# Main.net
KiCad netlist of a schematic drawn in Altium Designer
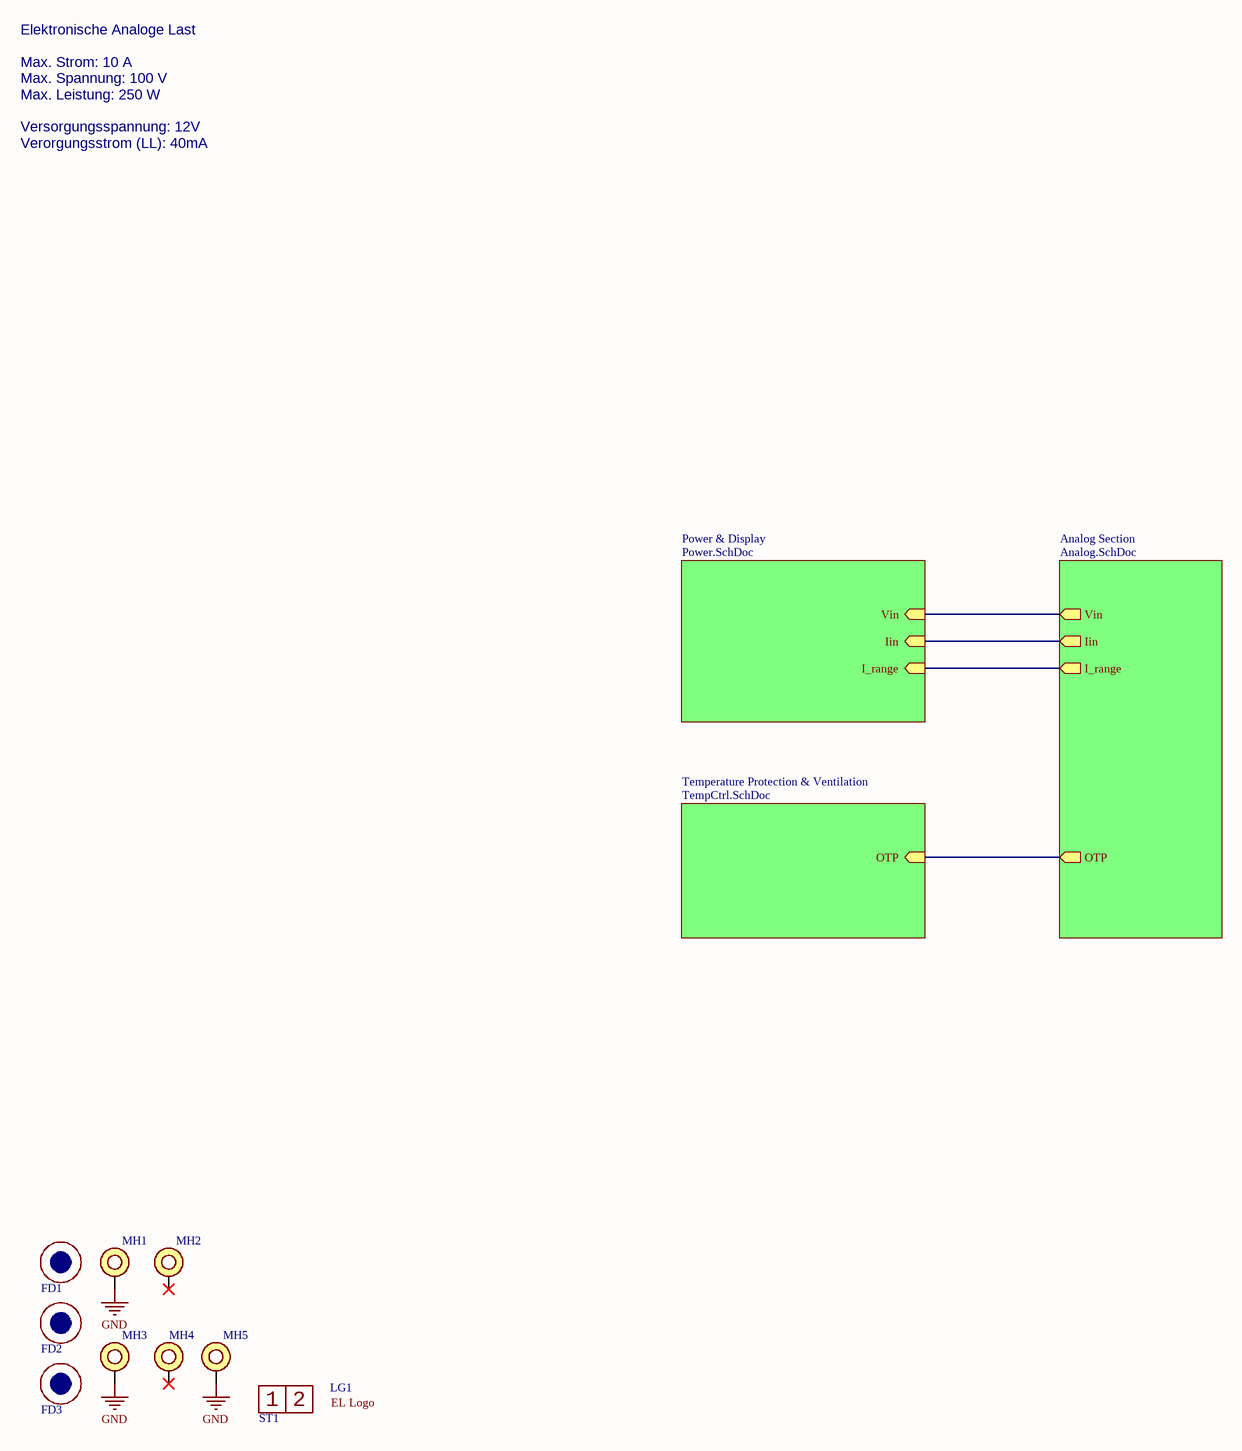
[diagram p0: Main.SchDoc]

(export (version "E")
  (design (tool "Eeschema 10.0.6"))
  (components
    (comp (ref "FD1")
      (value "Fiducial Mark 1mm")
      (footprint "Mech Fiducial 1mm")
      (description "Mech Fiducial Mark 1mm")
      (libsource (lib "SchLibrary") (part "Mech Fiducial"))
    )
    (comp (ref "FD2")
      (value "Fiducial Mark 1mm")
      (footprint "Mech Fiducial 1mm")
      (description "Mech Fiducial Mark 1mm")
      (libsource (lib "SchLibrary") (part "Mech Fiducial"))
    )
    (comp (ref "FD3")
      (value "Fiducial Mark 1mm")
      (footprint "Mech Fiducial 1mm")
      (description "Mech Fiducial Mark 1mm")
      (libsource (lib "SchLibrary") (part "Mech Fiducial"))
    )
    (comp (ref "LG1")
      (value "EL Logo")
      (footprint "Mech Logo EL")
      (description "Mech Logo EL Top Layer")
      (libsource (lib "SchLibrary") (part "Mech Logo EL"))
    )
    (comp (ref "MH1")
      (value "3.4mm")
      (footprint "Mech Hole 3.4mm Plated & Restring")
      (description "Mech Hole 3.4mm for M3 Plated & Restring")
      (libsource (lib "SchLibrary") (part "Mech Hole 3.4mm Pltd Restring 7mm"))
    )
    (comp (ref "MH2")
      (value "3.4mm")
      (footprint "Mech Hole 3.4mm Plated & Restring")
      (description "Mech Hole 3.4mm for M3 Plated & Restring")
      (libsource (lib "SchLibrary") (part "Mech Hole 3.4mm Pltd Restring 7mm"))
    )
    (comp (ref "MH3")
      (value "3.4mm")
      (footprint "Mech Hole 3.4mm Plated & Restring")
      (description "Mech Hole 3.4mm for M3 Plated & Restring")
      (libsource (lib "SchLibrary") (part "Mech Hole 3.4mm Pltd Restring 7mm"))
    )
    (comp (ref "MH4")
      (value "3.4mm")
      (footprint "Mech Hole 3.4mm Plated & Restring")
      (description "Mech Hole 3.4mm for M3 Plated & Restring")
      (libsource (lib "SchLibrary") (part "Mech Hole 3.4mm Pltd Restring 7mm"))
    )
    (comp (ref "MH5")
      (value "3.4mm")
      (footprint "Mech Hole 3.4mm Plated & Restring")
      (description "Mech Hole 3.4mm for M3 Plated & Restring")
      (libsource (lib "SchLibrary") (part "Mech Hole 3.4mm Pltd Restring 7mm"))
    )
    (comp (ref "ST1")
      (value "Layer Window 2")
      (footprint "Mech Layer Count 2")
      (description "Mech Layer Count 2 Layers")
      (libsource (lib "CustomLib") (part "Mech Layer Count 2"))
    )
  )
  (nets
    (net (code "5") (name "GND") (class "Default")
      (node (ref "MH1") (pin "1") (pinfunction "1_1") (pintype "power_in"))
      (node (ref "MH3") (pin "1") (pinfunction "1_1") (pintype "power_in"))
      (node (ref "MH5") (pin "1") (pinfunction "1_1") (pintype "power_in"))
    )
    (net (code "6") (name "unconnected-(FD1-Pad0)") (class "Default")
      (node (ref "FD1") (pin "0") (pinfunction "0_0") (pintype "passive"))
    )
    (net (code "7") (name "unconnected-(FD2-Pad0)") (class "Default")
      (node (ref "FD2") (pin "0") (pinfunction "0_0") (pintype "passive"))
    )
    (net (code "8") (name "unconnected-(FD3-Pad0)") (class "Default")
      (node (ref "FD3") (pin "0") (pinfunction "0_0") (pintype "passive"))
    )
    (net (code "9") (name "unconnected-(MH2-Pad1)") (class "Default")
      (node (ref "MH2") (pin "1") (pinfunction "1_1") (pintype "power_in+no_connect"))
    )
    (net (code "10") (name "unconnected-(MH4-Pad1)") (class "Default")
      (node (ref "MH4") (pin "1") (pinfunction "1_1") (pintype "power_in+no_connect"))
    )
  )
)
